# Main_Board.net
KiCad netlist of a schematic drawn in Altium Designer
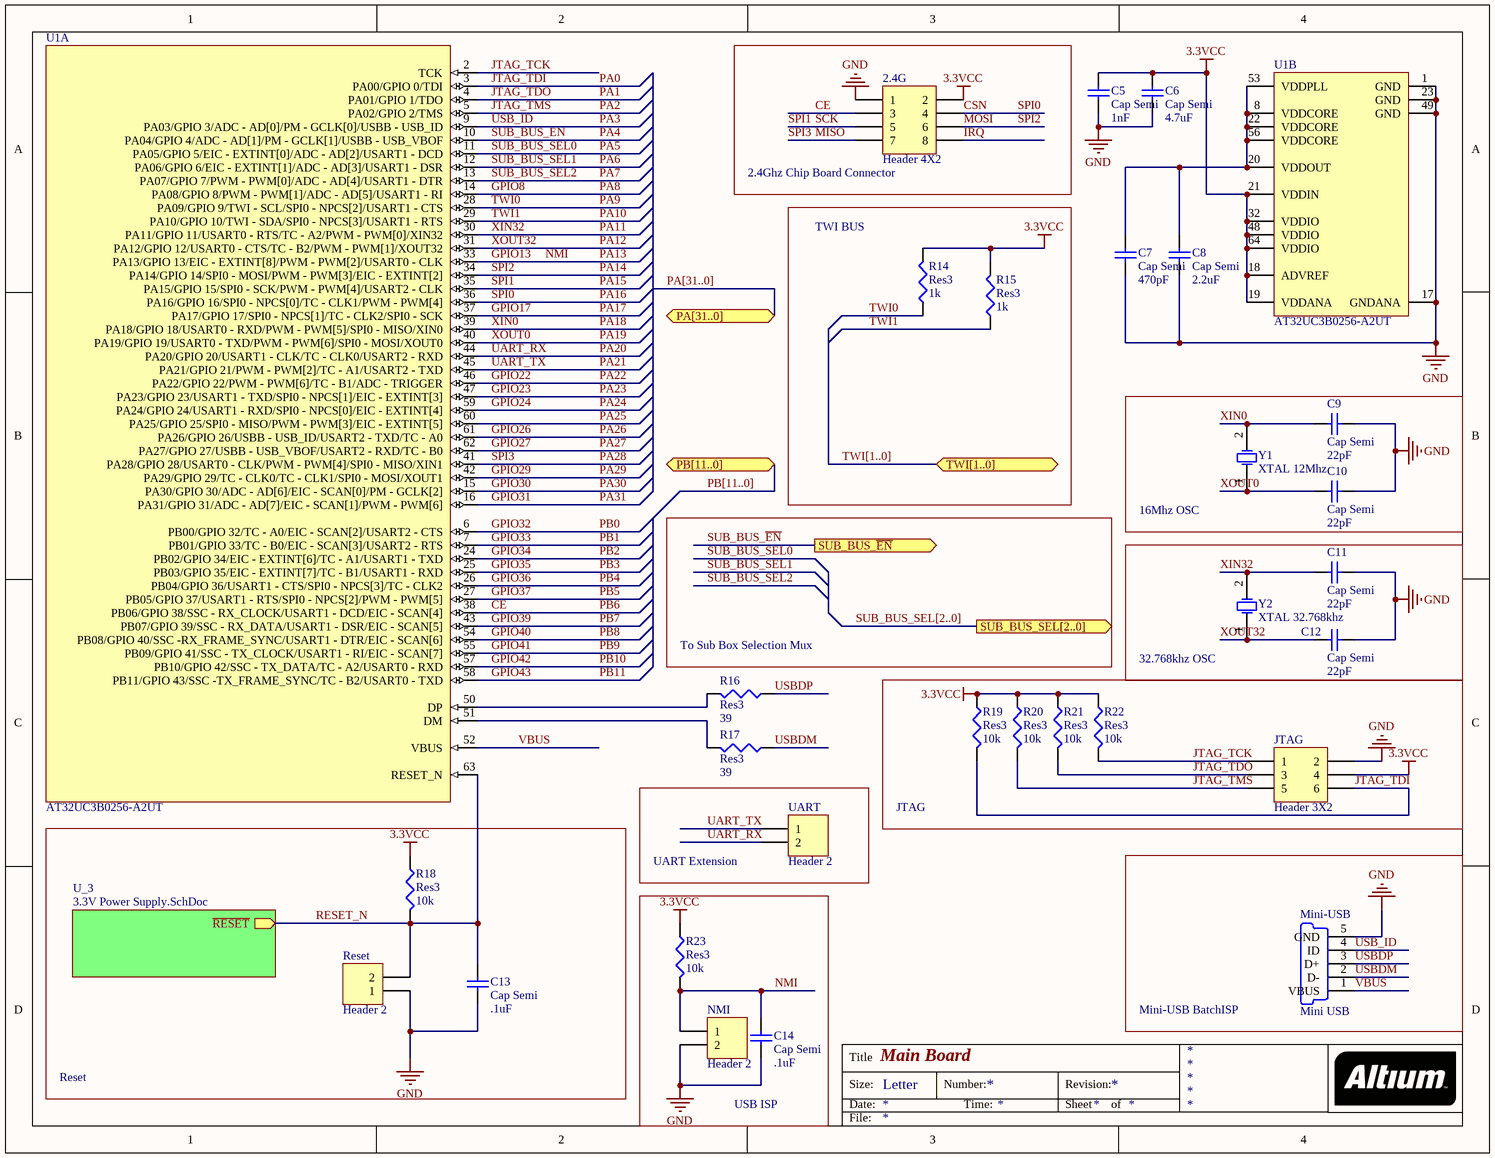
[diagram p0: Main Board.SchDoc]

(export (version "E")
  (design (tool "Eeschema 10.0.6"))
  (components
    (comp (ref "2.4G")
      (value "Header 4X2")
      (footprint "HDR2X4")
      (description "Header, 4-Pin, Dual row")
      (fields (field (name "PUBLISHER") "Altium Limited"))
      (libsource (lib "Miscellaneous Connectors") (part "Header 4X2"))
    )
    (comp (ref "C5")
      (value "Cap Semi")
      (footprint "CAPC2012N")
      (description "Capacitor (Semiconductor SIM Model)")
      (fields (field (name "ALTIUM_VALUE") "1nF") (field (name "PUBLISHER") "Altium Limited"))
      (libsource (lib "Miscellaneous Devices") (part "Cap Semi"))
    )
    (comp (ref "C6")
      (value "Cap Semi")
      (footprint "CAPC2012N")
      (description "Capacitor (Semiconductor SIM Model)")
      (fields (field (name "ALTIUM_VALUE") "4.7uF") (field (name "PUBLISHER") "Altium Limited"))
      (libsource (lib "Miscellaneous Devices") (part "Cap Semi"))
    )
    (comp (ref "C7")
      (value "Cap Semi")
      (footprint "CAPC2012N")
      (description "Capacitor (Semiconductor SIM Model)")
      (fields (field (name "ALTIUM_VALUE") "470pF") (field (name "PUBLISHER") "Altium Limited"))
      (libsource (lib "Miscellaneous Devices") (part "Cap Semi"))
    )
    (comp (ref "C8")
      (value "Cap Semi")
      (footprint "CAPC2012N")
      (description "Capacitor (Semiconductor SIM Model)")
      (fields (field (name "ALTIUM_VALUE") "2.2uF") (field (name "PUBLISHER") "Altium Limited"))
      (libsource (lib "Miscellaneous Devices") (part "Cap Semi"))
    )
    (comp (ref "C9")
      (value "Cap Semi")
      (footprint "CAPC2012N")
      (description "Capacitor (Semiconductor SIM Model)")
      (fields (field (name "ALTIUM_VALUE") "22pF") (field (name "PUBLISHER") "Altium Limited"))
      (libsource (lib "Miscellaneous Devices") (part "Cap Semi"))
    )
    (comp (ref "C10")
      (value "Cap Semi")
      (footprint "CAPC2012N")
      (description "Capacitor (Semiconductor SIM Model)")
      (fields (field (name "ALTIUM_VALUE") "22pF") (field (name "PUBLISHER") "Altium Limited"))
      (libsource (lib "Miscellaneous Devices") (part "Cap Semi"))
    )
    (comp (ref "C11")
      (value "Cap Semi")
      (footprint "CAPC2012N")
      (description "Capacitor (Semiconductor SIM Model)")
      (fields (field (name "ALTIUM_VALUE") "22pF") (field (name "PUBLISHER") "Altium Limited"))
      (libsource (lib "Miscellaneous Devices") (part "Cap Semi"))
    )
    (comp (ref "C12")
      (value "Cap Semi")
      (footprint "CAPC2012N")
      (description "Capacitor (Semiconductor SIM Model)")
      (fields (field (name "ALTIUM_VALUE") "22pF") (field (name "PUBLISHER") "Altium Limited"))
      (libsource (lib "Miscellaneous Devices") (part "Cap Semi"))
    )
    (comp (ref "C13")
      (value "Cap Semi")
      (footprint "CAPC2012N")
      (description "Capacitor (Semiconductor SIM Model)")
      (fields (field (name "ALTIUM_VALUE") ".1uF") (field (name "PUBLISHER") "Altium Limited"))
      (libsource (lib "Miscellaneous Devices") (part "Cap Semi"))
    )
    (comp (ref "C14")
      (value "Cap Semi")
      (footprint "CAPC2012N")
      (description "Capacitor (Semiconductor SIM Model)")
      (fields (field (name "ALTIUM_VALUE") ".1uF") (field (name "PUBLISHER") "Altium Limited"))
      (libsource (lib "Miscellaneous Devices") (part "Cap Semi"))
    )
    (comp (ref "JTAG")
      (value "Header 3X2")
      (footprint "HDR2X3")
      (description "Header, 3-Pin, Dual row")
      (fields (field (name "PUBLISHER") "Altium Limited"))
      (libsource (lib "Miscellaneous Connectors") (part "Header 3X2"))
    )
    (comp (ref "Mini-USB")
      (value "Mini USB")
      (footprint "MINI USB")
      (libsource (lib "Mini USB") (part "Mini USB"))
    )
    (comp (ref "NMI")
      (value "Header 2")
      (footprint "HDR1X2")
      (description "Header, 2-Pin")
      (fields (field (name "PUBLISHER") "Altium Limited"))
      (libsource (lib "Miscellaneous Connectors") (part "Header 2"))
    )
    (comp (ref "R14")
      (value "Res3")
      (footprint "RESC2012N")
      (description "Resistor")
      (fields (field (name "ALTIUM_VALUE") "1k") (field (name "PUBLISHER") "Altium Limited"))
      (libsource (lib "Miscellaneous Devices") (part "Res3"))
    )
    (comp (ref "R15")
      (value "Res3")
      (footprint "RESC2012N")
      (description "Resistor")
      (fields (field (name "ALTIUM_VALUE") "1k") (field (name "PUBLISHER") "Altium Limited"))
      (libsource (lib "Miscellaneous Devices") (part "Res3"))
    )
    (comp (ref "R16")
      (value "Res3")
      (footprint "RESC2012N")
      (description "Resistor")
      (fields (field (name "ALTIUM_VALUE") "39") (field (name "PUBLISHER") "Altium Limited"))
      (libsource (lib "Miscellaneous Devices") (part "Res3"))
    )
    (comp (ref "R17")
      (value "Res3")
      (footprint "RESC2012N")
      (description "Resistor")
      (fields (field (name "ALTIUM_VALUE") "39") (field (name "PUBLISHER") "Altium Limited"))
      (libsource (lib "Miscellaneous Devices") (part "Res3"))
    )
    (comp (ref "R18")
      (value "Res3")
      (footprint "RESC2012N")
      (description "Resistor")
      (fields (field (name "ALTIUM_VALUE") "10k") (field (name "PUBLISHER") "Altium Limited"))
      (libsource (lib "Miscellaneous Devices") (part "Res3"))
    )
    (comp (ref "R19")
      (value "Res3")
      (footprint "RESC2012N")
      (description "Resistor")
      (fields (field (name "ALTIUM_VALUE") "10k") (field (name "PUBLISHER") "Altium Limited"))
      (libsource (lib "Miscellaneous Devices") (part "Res3"))
    )
    (comp (ref "R20")
      (value "Res3")
      (footprint "RESC2012N")
      (description "Resistor")
      (fields (field (name "ALTIUM_VALUE") "10k") (field (name "PUBLISHER") "Altium Limited"))
      (libsource (lib "Miscellaneous Devices") (part "Res3"))
    )
    (comp (ref "R21")
      (value "Res3")
      (footprint "RESC2012N")
      (description "Resistor")
      (fields (field (name "ALTIUM_VALUE") "10k") (field (name "PUBLISHER") "Altium Limited"))
      (libsource (lib "Miscellaneous Devices") (part "Res3"))
    )
    (comp (ref "R22")
      (value "Res3")
      (footprint "RESC2012N")
      (description "Resistor")
      (fields (field (name "ALTIUM_VALUE") "10k") (field (name "PUBLISHER") "Altium Limited"))
      (libsource (lib "Miscellaneous Devices") (part "Res3"))
    )
    (comp (ref "R23")
      (value "Res3")
      (footprint "RESC2012N")
      (description "Resistor")
      (fields (field (name "ALTIUM_VALUE") "10k") (field (name "PUBLISHER") "Altium Limited"))
      (libsource (lib "Miscellaneous Devices") (part "Res3"))
    )
    (comp (ref "Reset")
      (value "Header 2")
      (footprint "HDR1X2")
      (description "Header, 2-Pin")
      (fields (field (name "PUBLISHER") "Altium Limited"))
      (libsource (lib "") (part "Header 2_1"))
    )
    (comp (ref "U1")
      (value "AT32UC3B0256-A2UT")
      (footprint "TQFP64_N - ECESHOP")
      (fields (field (name "PUBLISHER") "Altium Limited"))
      (libsource (lib "Atmel Microcontroller 32-Bit AVR UC3") (part "AT32UC3B0256-A2UT"))
    )
    (comp (ref "UART")
      (value "Header 2")
      (footprint "HDR1X2")
      (description "Header, 2-Pin")
      (fields (field (name "PUBLISHER") "Altium Limited"))
      (libsource (lib "Miscellaneous Connectors") (part "Header 2"))
    )
    (comp (ref "Y1")
      (value "XTAL 12Mhz")
      (footprint "HC-49U - Through Hole")
      (description "Crystal Oscillator")
      (fields (field (name "PUBLISHER") "Altium Limited"))
      (libsource (lib "Miscellaneous Devices") (part "XTAL"))
    )
    (comp (ref "Y2")
      (value "XTAL 32.768khz")
      (footprint "XTAL32.768")
      (description "Crystal Oscillator")
      (fields (field (name "PUBLISHER") "Altium Limited"))
      (libsource (lib "Miscellaneous Devices") (part "XTAL"))
    )
  )
  (nets
    (net (code "1") (name "/IRQ") (class "Default")
      (node (ref "2.4G") (pin "8") (pinfunction "8_8") (pintype "passive"))
    )
    (net (code "2") (name "/JTAG_TCK") (class "Default")
      (node (ref "JTAG") (pin "1") (pinfunction "1_1") (pintype "passive"))
      (node (ref "R22") (pin "2") (pinfunction "2_2") (pintype "passive"))
      (node (ref "U1") (pin "2") (pinfunction "TCK_2") (pintype "input"))
    )
    (net (code "3") (name "/PA0") (class "Default")
      (node (ref "JTAG") (pin "6") (pinfunction "6_6") (pintype "passive"))
      (node (ref "R19") (pin "2") (pinfunction "2_2") (pintype "passive"))
      (node (ref "U1") (pin "3") (pinfunction "PA00/GPIO_0/TDI_3") (pintype "bidirectional"))
    )
    (net (code "4") (name "/PA1") (class "Default")
      (node (ref "JTAG") (pin "3") (pinfunction "3_3") (pintype "passive"))
      (node (ref "R21") (pin "2") (pinfunction "2_2") (pintype "passive"))
      (node (ref "U1") (pin "4") (pinfunction "PA01/GPIO_1/TDO_4") (pintype "bidirectional"))
    )
    (net (code "5") (name "/PA2") (class "Default")
      (node (ref "JTAG") (pin "5") (pinfunction "5_5") (pintype "passive"))
      (node (ref "R20") (pin "2") (pinfunction "2_2") (pintype "passive"))
      (node (ref "U1") (pin "5") (pinfunction "PA02/GPIO_2/TMS_5") (pintype "bidirectional"))
    )
    (net (code "6") (name "/PA3") (class "Default")
      (node (ref "Mini-USB") (pin "4") (pinfunction "ID_4") (pintype "passive"))
      (node (ref "U1") (pin "9") (pinfunction "PA03/GPIO_3/ADC_-_AD[0]/PM_-_GCLK[0]/USBB_-_USB_ID_9") (pintype "bidirectional"))
    )
    (net (code "7") (name "/PA4") (class "Default")
      (node (ref "U1") (pin "10") (pinfunction "PA04/GPIO_4/ADC_-_AD[1]/PM_-_GCLK[1]/USBB_-_USB_VBOF_10") (pintype "bidirectional"))
    )
    (net (code "8") (name "/PA5") (class "Default")
      (node (ref "U1") (pin "11") (pinfunction "PA05/GPIO_5/EIC_-_EXTINT[0]/ADC_-_AD[2]/USART1_-_DCD_11") (pintype "bidirectional"))
    )
    (net (code "9") (name "/PA6") (class "Default")
      (node (ref "U1") (pin "12") (pinfunction "PA06/GPIO_6/EIC_-_EXTINT[1]/ADC_-_AD[3]/USART1_-_DSR_12") (pintype "bidirectional"))
    )
    (net (code "10") (name "/PA7") (class "Default")
      (node (ref "U1") (pin "13") (pinfunction "PA07/GPIO_7/PWM_-_PWM[0]/ADC_-_AD[4]/USART1_-_DTR_13") (pintype "bidirectional"))
    )
    (net (code "11") (name "/PA8") (class "Default")
      (node (ref "U1") (pin "14") (pinfunction "PA08/GPIO_8/PWM_-_PWM[1]/ADC_-_AD[5]/USART1_-_RI_14") (pintype "bidirectional"))
    )
    (net (code "12") (name "/PA11") (class "Default")
      (node (ref "C11") (pin "2") (pinfunction "2_2") (pintype "passive"))
      (node (ref "U1") (pin "30") (pinfunction "PA11/GPIO_11/USART0_-_RTS/TC_-_A2/PWM_-_PWM[0]/XIN32_30") (pintype "bidirectional"))
      (node (ref "Y2") (pin "2") (pinfunction "OSC2_2") (pintype "passive"))
    )
    (net (code "13") (name "/PA12") (class "Default")
      (node (ref "C12") (pin "2") (pinfunction "2_2") (pintype "passive"))
      (node (ref "U1") (pin "31") (pinfunction "PA12/GPIO_12/USART0_-_CTS/TC_-_B2/PWM_-_PWM[1]/XOUT32_31") (pintype "bidirectional"))
      (node (ref "Y2") (pin "1") (pinfunction "OSC1_1") (pintype "passive"))
    )
    (net (code "14") (name "/PA13") (class "Default")
      (node (ref "C14") (pin "1") (pinfunction "1_1") (pintype "passive"))
      (node (ref "NMI") (pin "1") (pinfunction "1_1") (pintype "passive"))
      (node (ref "R23") (pin "2") (pinfunction "2_2") (pintype "passive"))
      (node (ref "U1") (pin "33") (pinfunction "PA13/GPIO_13/EIC_-_EXTINT[8]/PWM_-_PWM[2]/USART0_-_CLK_33") (pintype "bidirectional"))
    )
    (net (code "15") (name "/PA14") (class "Default")
      (node (ref "2.4G") (pin "6") (pinfunction "6_6") (pintype "passive"))
      (node (ref "U1") (pin "34") (pinfunction "PA14/GPIO_14/SPI0_-_MOSI/PWM_-_PWM[3]/EIC_-_EXTINT[2]_34") (pintype "bidirectional"))
    )
    (net (code "16") (name "/PA15") (class "Default")
      (node (ref "2.4G") (pin "5") (pinfunction "5_5") (pintype "passive"))
      (node (ref "U1") (pin "35") (pinfunction "PA15/GPIO_15/SPI0_-_SCK/PWM_-_PWM[4]/USART2_-_CLK_35") (pintype "bidirectional"))
    )
    (net (code "17") (name "/PA16") (class "Default")
      (node (ref "2.4G") (pin "4") (pinfunction "4_4") (pintype "passive"))
      (node (ref "U1") (pin "36") (pinfunction "PA16/GPIO_16/SPI0_-_NPCS[0]/TC_-_CLK1/PWM_-_PWM[4]_36") (pintype "bidirectional"))
    )
    (net (code "18") (name "/PA17") (class "Default")
      (node (ref "U1") (pin "37") (pinfunction "PA17/GPIO_17/SPI0_-_NPCS[1]/TC_-_CLK2/SPI0_-_SCK_37") (pintype "bidirectional"))
    )
    (net (code "19") (name "/PA18") (class "Default")
      (node (ref "C9") (pin "2") (pinfunction "2_2") (pintype "passive"))
      (node (ref "U1") (pin "39") (pinfunction "PA18/GPIO_18/USART0_-_RXD/PWM_-_PWM[5]/SPI0_-_MISO/XIN0_39") (pintype "bidirectional"))
      (node (ref "Y1") (pin "2") (pinfunction "OSC2_2") (pintype "passive"))
    )
    (net (code "20") (name "/PA19") (class "Default")
      (node (ref "C10") (pin "2") (pinfunction "2_2") (pintype "passive"))
      (node (ref "U1") (pin "40") (pinfunction "PA19/GPIO_19/USART0_-_TXD/PWM_-_PWM[6]/SPI0_-_MOSI/XOUT0_40") (pintype "bidirectional"))
      (node (ref "Y1") (pin "1") (pinfunction "OSC1_1") (pintype "passive"))
    )
    (net (code "21") (name "/PA20") (class "Default")
      (node (ref "U1") (pin "44") (pinfunction "PA20/GPIO_20/USART1_-_CLK/TC_-_CLK0/USART2_-_RXD_44") (pintype "bidirectional"))
      (node (ref "UART") (pin "2") (pinfunction "2_2") (pintype "passive"))
    )
    (net (code "22") (name "/PA21") (class "Default")
      (node (ref "U1") (pin "45") (pinfunction "PA21/GPIO_21/PWM_-_PWM[2]/TC_-_A1/USART2_-_TXD_45") (pintype "bidirectional"))
      (node (ref "UART") (pin "1") (pinfunction "1_1") (pintype "passive"))
    )
    (net (code "23") (name "/PA22") (class "Default")
      (node (ref "U1") (pin "46") (pinfunction "PA22/GPIO_22/PWM_-_PWM[6]/TC_-_B1/ADC_-_TRIGGER_46") (pintype "bidirectional"))
    )
    (net (code "24") (name "/PA23") (class "Default")
      (node (ref "U1") (pin "47") (pinfunction "PA23/GPIO_23/USART1_-_TXD/SPI0_-_NPCS[1]/EIC_-_EXTINT[3]_47") (pintype "bidirectional"))
    )
    (net (code "25") (name "/PA24") (class "Default")
      (node (ref "U1") (pin "59") (pinfunction "PA24/GPIO_24/USART1_-_RXD/SPI0_-_NPCS[0]/EIC_-_EXTINT[4]_59") (pintype "bidirectional"))
    )
    (net (code "26") (name "/PA25") (class "Default")
      (node (ref "U1") (pin "60") (pinfunction "PA25/GPIO_25/SPI0_-_MISO/PWM_-_PWM[3]/EIC_-_EXTINT[5]_60") (pintype "bidirectional"))
    )
    (net (code "27") (name "/PA26") (class "Default")
      (node (ref "U1") (pin "61") (pinfunction "PA26/GPIO_26/USBB_-_USB_ID/USART2_-_TXD/TC_-_A0_61") (pintype "bidirectional"))
    )
    (net (code "28") (name "/PA27") (class "Default")
      (node (ref "U1") (pin "62") (pinfunction "PA27/GPIO_27/USBB_-_USB_VBOF/USART2_-_RXD/TC_-_B0_62") (pintype "bidirectional"))
    )
    (net (code "29") (name "/PA28") (class "Default")
      (node (ref "2.4G") (pin "7") (pinfunction "7_7") (pintype "passive"))
      (node (ref "U1") (pin "41") (pinfunction "PA28/GPIO_28/USART0_-_CLK/PWM_-_PWM[4]/SPI0_-_MISO/XIN1_41") (pintype "bidirectional"))
    )
    (net (code "30") (name "/PA29") (class "Default")
      (node (ref "U1") (pin "42") (pinfunction "PA29/GPIO_29/TC_-_CLK0/TC_-_CLK1/SPI0_-_MOSI/XOUT1_42") (pintype "bidirectional"))
    )
    (net (code "31") (name "/PA30") (class "Default")
      (node (ref "U1") (pin "15") (pinfunction "PA30/GPIO_30/ADC_-_AD[6]/EIC_-_SCAN[0]/PM_-_GCLK[2]_15") (pintype "bidirectional"))
    )
    (net (code "32") (name "/PA31") (class "Default")
      (node (ref "U1") (pin "16") (pinfunction "PA31/GPIO_31/ADC_-_AD[7]/EIC_-_SCAN[1]/PWM_-_PWM[6]_16") (pintype "bidirectional"))
    )
    (net (code "34") (name "/PB0") (class "Default")
      (node (ref "U1") (pin "6") (pinfunction "PB00/GPIO_32/TC_-_A0/EIC_-_SCAN[2]/USART2_-_CTS_6") (pintype "bidirectional"))
    )
    (net (code "35") (name "/PB1") (class "Default")
      (node (ref "U1") (pin "7") (pinfunction "PB01/GPIO_33/TC_-_B0/EIC_-_SCAN[3]/USART2_-_RTS_7") (pintype "bidirectional"))
    )
    (net (code "36") (name "/PB2") (class "Default")
      (node (ref "U1") (pin "24") (pinfunction "PB02/GPIO_34/EIC_-_EXTINT[6]/TC_-_A1/USART1_-_TXD_24") (pintype "bidirectional"))
    )
    (net (code "37") (name "/PB3") (class "Default")
      (node (ref "U1") (pin "25") (pinfunction "PB03/GPIO_35/EIC_-_EXTINT[7]/TC_-_B1/USART1_-_RXD_25") (pintype "bidirectional"))
    )
    (net (code "38") (name "/PB4") (class "Default")
      (node (ref "U1") (pin "26") (pinfunction "PB04/GPIO_36/USART1_-_CTS/SPI0_-_NPCS[3]/TC_-_CLK2_26") (pintype "bidirectional"))
    )
    (net (code "39") (name "/PB5") (class "Default")
      (node (ref "U1") (pin "27") (pinfunction "PB05/GPIO_37/USART1_-_RTS/SPI0_-_NPCS[2]/PWM_-_PWM[5]_27") (pintype "bidirectional"))
    )
    (net (code "40") (name "/PB6") (class "Default")
      (node (ref "2.4G") (pin "3") (pinfunction "3_3") (pintype "passive"))
      (node (ref "U1") (pin "38") (pinfunction "PB06/GPIO_38/SSC_-_RX_CLOCK/USART1_-_DCD/EIC_-_SCAN[4]_38") (pintype "bidirectional"))
    )
    (net (code "41") (name "/PB7") (class "Default")
      (node (ref "U1") (pin "43") (pinfunction "PB07/GPIO_39/SSC_-_RX_DATA/USART1_-_DSR/EIC_-_SCAN[5]_43") (pintype "bidirectional"))
    )
    (net (code "42") (name "/PB8") (class "Default")
      (node (ref "U1") (pin "54") (pinfunction "PB08/GPIO_40/SSC_-RX_FRAME_SYNC/USART1_-_DTR/EIC_-_SCAN[6]_54") (pintype "bidirectional"))
    )
    (net (code "43") (name "/PB9") (class "Default")
      (node (ref "U1") (pin "55") (pinfunction "PB09/GPIO_41/SSC_-_TX_CLOCK/USART1_-_RI/EIC_-_SCAN[7]_55") (pintype "bidirectional"))
    )
    (net (code "44") (name "/PB10") (class "Default")
      (node (ref "U1") (pin "57") (pinfunction "PB10/GPIO_42/SSC_-_TX_DATA/TC_-_A2/USART0_-_RXD_57") (pintype "bidirectional"))
    )
    (net (code "45") (name "/PB11") (class "Default")
      (node (ref "U1") (pin "58") (pinfunction "PB11/GPIO_43/SSC_-TX_FRAME_SYNC/TC_-_B2/USART0_-_TXD_58") (pintype "bidirectional"))
    )
    (net (code "47") (name "/RESET_N") (class "Default")
      (node (ref "C13") (pin "1") (pinfunction "1_1") (pintype "passive"))
      (node (ref "R18") (pin "2") (pinfunction "2_2") (pintype "passive"))
      (node (ref "Reset") (pin "2") (pinfunction "2_2") (pintype "passive"))
      (node (ref "U1") (pin "63") (pinfunction "RESET_N_63") (pintype "input"))
    )
    (net (code "49") (name "/TWI0") (class "Default")
      (node (ref "R14") (pin "1") (pinfunction "1_1") (pintype "passive"))
      (node (ref "U1") (pin "28") (pinfunction "PA09/GPIO_9/TWI_-_SCL/SPI0_-_NPCS[2]/USART1_-_CTS_28") (pintype "bidirectional"))
    )
    (net (code "50") (name "/TWI1") (class "Default")
      (node (ref "R15") (pin "1") (pinfunction "1_1") (pintype "passive"))
      (node (ref "U1") (pin "29") (pinfunction "PA10/GPIO_10/TWI_-_SDA/SPI0_-_NPCS[3]/USART1_-_RTS_29") (pintype "bidirectional"))
    )
    (net (code "52") (name "/USBDM") (class "Default")
      (node (ref "Mini-USB") (pin "2") (pinfunction "D-_2") (pintype "passive"))
      (node (ref "R17") (pin "1") (pinfunction "1_1") (pintype "passive"))
    )
    (net (code "53") (name "/USBDP") (class "Default")
      (node (ref "Mini-USB") (pin "3") (pinfunction "D+_3") (pintype "passive"))
      (node (ref "R16") (pin "1") (pinfunction "1_1") (pintype "passive"))
    )
    (net (code "54") (name "/VBUS") (class "Default")
      (node (ref "Mini-USB") (pin "1") (pinfunction "VBUS_1") (pintype "passive"))
      (node (ref "U1") (pin "52") (pinfunction "VBUS_52") (pintype "input"))
    )
    (net (code "55") (name "3.3VCC") (class "Default")
      (node (ref "2.4G") (pin "2") (pinfunction "2_2") (pintype "passive"))
      (node (ref "C5") (pin "2") (pinfunction "2_2") (pintype "passive"))
      (node (ref "C6") (pin "2") (pinfunction "2_2") (pintype "passive"))
      (node (ref "JTAG") (pin "4") (pinfunction "4_4") (pintype "passive"))
      (node (ref "R14") (pin "2") (pinfunction "2_2") (pintype "passive"))
      (node (ref "R15") (pin "2") (pinfunction "2_2") (pintype "passive"))
      (node (ref "R18") (pin "1") (pinfunction "1_1") (pintype "passive"))
      (node (ref "R19") (pin "1") (pinfunction "1_1") (pintype "passive"))
      (node (ref "R20") (pin "1") (pinfunction "1_1") (pintype "passive"))
      (node (ref "R21") (pin "1") (pinfunction "1_1") (pintype "passive"))
      (node (ref "R22") (pin "1") (pinfunction "1_1") (pintype "passive"))
      (node (ref "R23") (pin "1") (pinfunction "1_1") (pintype "passive"))
      (node (ref "U1") (pin "18") (pinfunction "ADVREF_18") (pintype "power_in"))
      (node (ref "U1") (pin "19") (pinfunction "VDDANA_19") (pintype "power_in"))
      (node (ref "U1") (pin "21") (pinfunction "VDDIN_21") (pintype "power_in"))
      (node (ref "U1") (pin "32") (pinfunction "VDDIO_32") (pintype "power_in"))
      (node (ref "U1") (pin "48") (pinfunction "VDDIO_48") (pintype "power_in"))
      (node (ref "U1") (pin "64") (pinfunction "VDDIO_64") (pintype "power_in"))
    )
    (net (code "56") (name "GND") (class "Default")
      (node (ref "2.4G") (pin "1") (pinfunction "1_1") (pintype "passive"))
      (node (ref "C10") (pin "1") (pinfunction "1_1") (pintype "passive"))
      (node (ref "C11") (pin "1") (pinfunction "1_1") (pintype "passive"))
      (node (ref "C12") (pin "1") (pinfunction "1_1") (pintype "passive"))
      (node (ref "C13") (pin "2") (pinfunction "2_2") (pintype "passive"))
      (node (ref "C14") (pin "2") (pinfunction "2_2") (pintype "passive"))
      (node (ref "C5") (pin "1") (pinfunction "1_1") (pintype "passive"))
      (node (ref "C6") (pin "1") (pinfunction "1_1") (pintype "passive"))
      (node (ref "C7") (pin "1") (pinfunction "1_1") (pintype "passive"))
      (node (ref "C8") (pin "1") (pinfunction "1_1") (pintype "passive"))
      (node (ref "C9") (pin "1") (pinfunction "1_1") (pintype "passive"))
      (node (ref "JTAG") (pin "2") (pinfunction "2_2") (pintype "passive"))
      (node (ref "Mini-USB") (pin "5") (pinfunction "GND_5") (pintype "passive"))
      (node (ref "NMI") (pin "2") (pinfunction "2_2") (pintype "passive"))
      (node (ref "Reset") (pin "1") (pinfunction "1_1") (pintype "passive"))
      (node (ref "U1") (pin "1") (pinfunction "GND_1") (pintype "power_in"))
      (node (ref "U1") (pin "17") (pinfunction "GNDANA_17") (pintype "power_in"))
      (node (ref "U1") (pin "23") (pinfunction "GND_23") (pintype "power_in"))
      (node (ref "U1") (pin "49") (pinfunction "GND_49") (pintype "power_in"))
    )
    (net (code "57") (name "Net-(U1A-DM)") (class "Default")
      (node (ref "R17") (pin "2") (pinfunction "2_2") (pintype "passive"))
      (node (ref "U1") (pin "51") (pinfunction "DM_51") (pintype "input"))
    )
    (net (code "58") (name "Net-(U1A-DP)") (class "Default")
      (node (ref "R16") (pin "2") (pinfunction "2_2") (pintype "passive"))
      (node (ref "U1") (pin "50") (pinfunction "DP_50") (pintype "input"))
    )
    (net (code "59") (name "Net-(U1B-VDDOUT)") (class "Default")
      (node (ref "C7") (pin "2") (pinfunction "2_2") (pintype "passive"))
      (node (ref "C8") (pin "2") (pinfunction "2_2") (pintype "passive"))
      (node (ref "U1") (pin "20") (pinfunction "VDDOUT_20") (pintype "power_in"))
      (node (ref "U1") (pin "22") (pinfunction "VDDCORE_22") (pintype "power_in"))
      (node (ref "U1") (pin "53") (pinfunction "VDDPLL_53") (pintype "power_in"))
      (node (ref "U1") (pin "56") (pinfunction "VDDCORE_56") (pintype "power_in"))
      (node (ref "U1") (pin "8") (pinfunction "VDDCORE_8") (pintype "power_in"))
    )
  )
)
